# SCH_Carte_des_boutons_capacitives_2025-0.net
KiCad netlist of a schematic drawn in EasyEDA
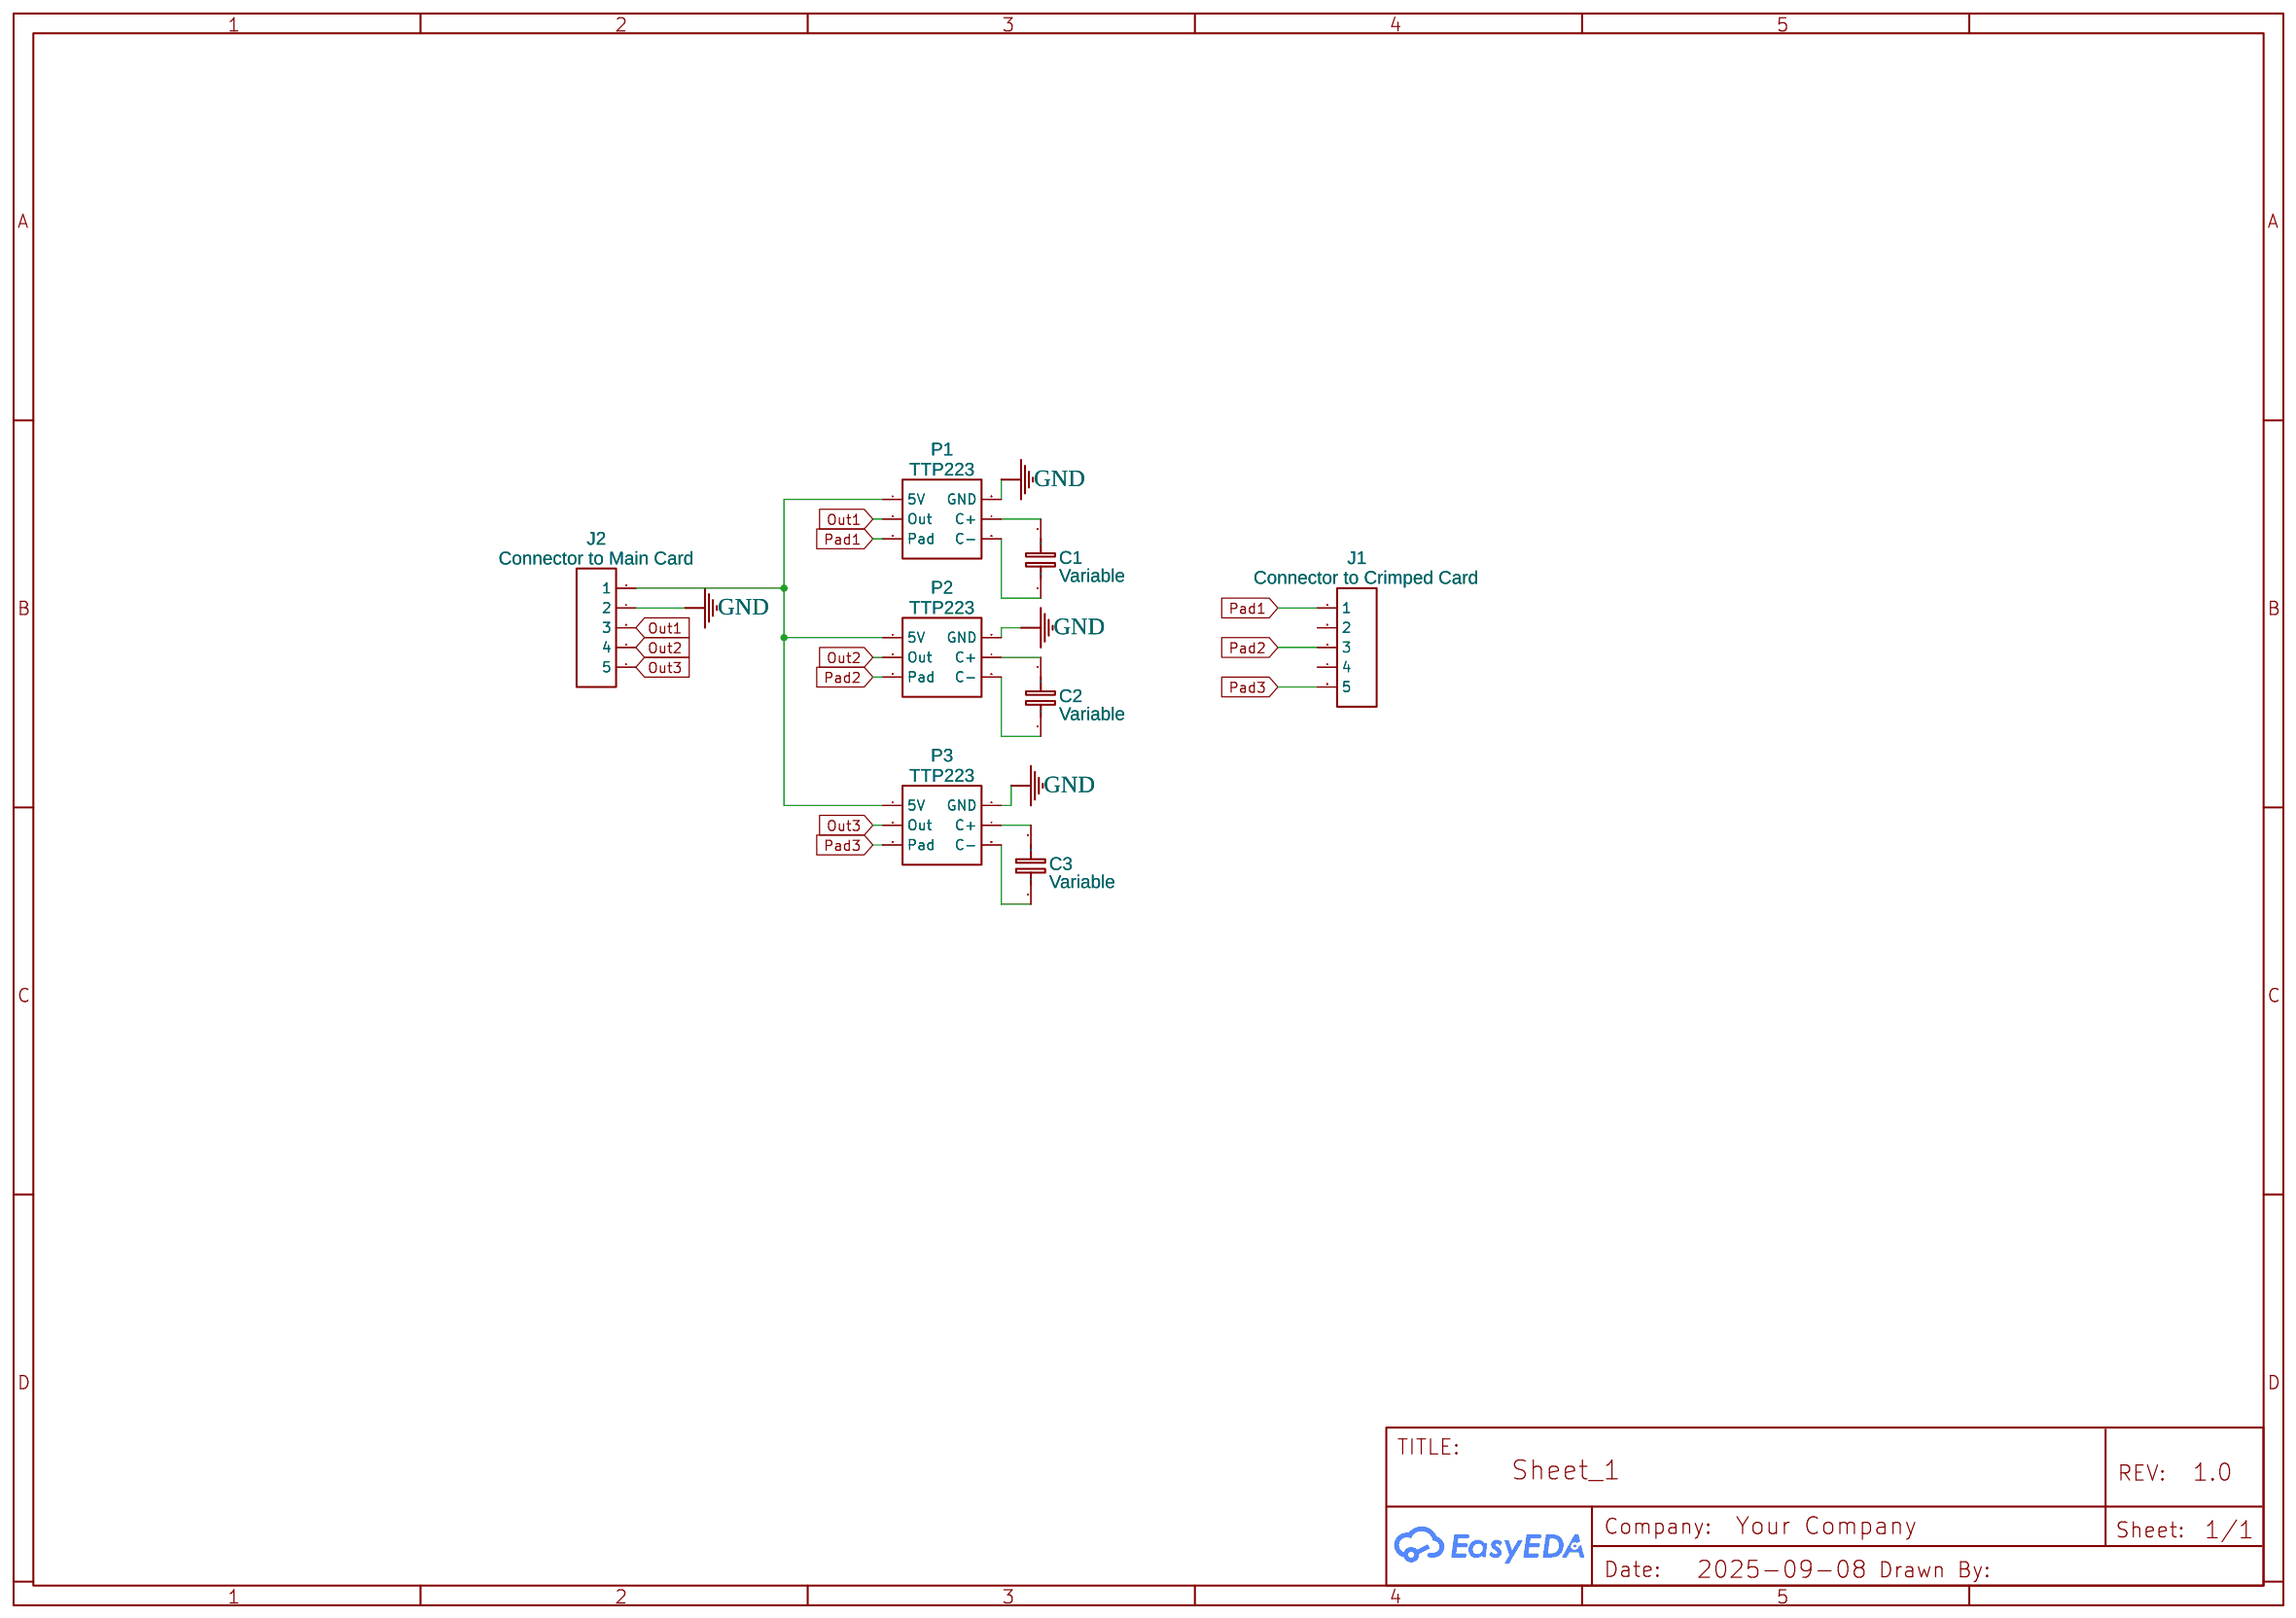
[diagram p0: schematic sheet]

(export (version "E")
  (design (tool "Eeschema 10.0.6"))
  (components
    (comp (ref "C1") (value "Variable") (libsource (lib "") (part "C_0603_EU_1")))
    (comp (ref "C2") (value "Variable") (libsource (lib "") (part "C_0603_EU")))
    (comp (ref "C3") (value "Variable") (libsource (lib "") (part "C_0603_EU")))
    (comp (ref "J1") (value "Connector to Crimped Card") (libsource (lib "") (part "HDR-M-2.54_1x5")))
    (comp (ref "J2") (value "Connector to Main Card") (libsource (lib "") (part "HDR-M-2.54_1x5_1")))
    (comp (ref "P1")
      (value "TTP223")
      (fields (field (name "Manufacturer Part") "2X3 2.54mm IDC Box") (field (name "Manufacturer") "BOOMELE"))
      (libsource (lib "") (part "HDR-IDC-2.54-2X3P"))
    )
    (comp (ref "P2")
      (value "TTP223")
      (fields (field (name "Manufacturer Part") "2X3 2.54mm IDC Box") (field (name "Manufacturer") "BOOMELE"))
      (libsource (lib "") (part "HDR-IDC-2.54-2X3P"))
    )
    (comp (ref "P3")
      (value "TTP223")
      (fields (field (name "Manufacturer Part") "2X3 2.54mm IDC Box") (field (name "Manufacturer") "BOOMELE"))
      (libsource (lib "") (part "HDR-IDC-2.54-2X3P"))
    )
  )
  (nets
    (net (code "1") (name "GND") (class "Default")
      (node (ref "J2") (pin "4") (pinfunction "2_4") (pintype "unspecified"))
      (node (ref "P1") (pin "2") (pinfunction "GND_2") (pintype "unspecified"))
      (node (ref "P2") (pin "2") (pinfunction "GND_2") (pintype "unspecified"))
      (node (ref "P3") (pin "2") (pinfunction "GND_2") (pintype "unspecified"))
    )
    (net (code "2") (name "Net-(J2-1)") (class "Default")
      (node (ref "J2") (pin "5") (pinfunction "1_5") (pintype "unspecified"))
      (node (ref "P1") (pin "1") (pinfunction "5V_1") (pintype "unspecified"))
      (node (ref "P2") (pin "1") (pinfunction "5V_1") (pintype "unspecified"))
      (node (ref "P3") (pin "1") (pinfunction "5V_1") (pintype "unspecified"))
    )
    (net (code "3") (name "Net-(P1-C+)") (class "Default")
      (node (ref "C1") (pin "2") (pinfunction "2_2") (pintype "unspecified"))
      (node (ref "P1") (pin "4") (pinfunction "C+_4") (pintype "unspecified"))
    )
    (net (code "4") (name "Net-(P1-C-)") (class "Default")
      (node (ref "C1") (pin "1") (pinfunction "1_1") (pintype "unspecified"))
      (node (ref "P1") (pin "6") (pinfunction "C-_6") (pintype "unspecified"))
    )
    (net (code "5") (name "Net-(P2-C+)") (class "Default")
      (node (ref "C2") (pin "2") (pinfunction "2_2") (pintype "unspecified"))
      (node (ref "P2") (pin "4") (pinfunction "C+_4") (pintype "unspecified"))
    )
    (net (code "6") (name "Net-(P2-C-)") (class "Default")
      (node (ref "C2") (pin "1") (pinfunction "1_1") (pintype "unspecified"))
      (node (ref "P2") (pin "6") (pinfunction "C-_6") (pintype "unspecified"))
    )
    (net (code "7") (name "Net-(P3-C+)") (class "Default")
      (node (ref "C3") (pin "2") (pinfunction "2_2") (pintype "unspecified"))
      (node (ref "P3") (pin "4") (pinfunction "C+_4") (pintype "unspecified"))
    )
    (net (code "8") (name "Net-(P3-C-)") (class "Default")
      (node (ref "C3") (pin "1") (pinfunction "1_1") (pintype "unspecified"))
      (node (ref "P3") (pin "6") (pinfunction "C-_6") (pintype "unspecified"))
    )
    (net (code "9") (name "Out1") (class "Default")
      (node (ref "J2") (pin "3") (pinfunction "3_3") (pintype "unspecified"))
      (node (ref "P1") (pin "3") (pinfunction "Out_3") (pintype "unspecified"))
    )
    (net (code "10") (name "Out2") (class "Default")
      (node (ref "J2") (pin "2") (pinfunction "4_2") (pintype "unspecified"))
      (node (ref "P2") (pin "3") (pinfunction "Out_3") (pintype "unspecified"))
    )
    (net (code "11") (name "Out3") (class "Default")
      (node (ref "J2") (pin "1") (pinfunction "5_1") (pintype "unspecified"))
      (node (ref "P3") (pin "3") (pinfunction "Out_3") (pintype "unspecified"))
    )
    (net (code "12") (name "Pad1") (class "Default")
      (node (ref "J1") (pin "1") (pinfunction "1_1") (pintype "unspecified"))
      (node (ref "P1") (pin "5") (pinfunction "Pad_5") (pintype "unspecified"))
    )
    (net (code "13") (name "Pad2") (class "Default")
      (node (ref "J1") (pin "3") (pinfunction "3_3") (pintype "unspecified"))
      (node (ref "P2") (pin "5") (pinfunction "Pad_5") (pintype "unspecified"))
    )
    (net (code "14") (name "Pad3") (class "Default")
      (node (ref "J1") (pin "5") (pinfunction "5_5") (pintype "unspecified"))
      (node (ref "P3") (pin "5") (pinfunction "Pad_5") (pintype "unspecified"))
    )
    (net (code "15") (name "unconnected-(J1-Pad2)") (class "Default")
      (node (ref "J1") (pin "2") (pinfunction "2_2") (pintype "unspecified"))
    )
    (net (code "16") (name "unconnected-(J1-Pad4)") (class "Default")
      (node (ref "J1") (pin "4") (pinfunction "4_4") (pintype "unspecified"))
    )
  )
)
